# Charger_Relay_Board_rev2.net
KiCad netlist of a schematic drawn in EAGLE
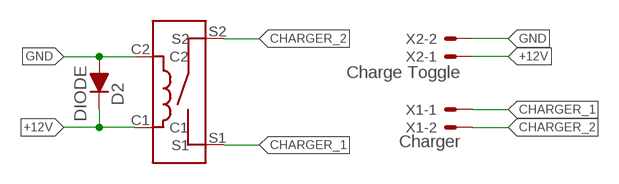
[diagram p0: schematic, sheet 1]

(export (version "E")
  (design (tool "Eeschema 10.0.6"))
  (components
    (comp (ref "D2")
      (value "DIODE")
      (footprint "eagle-import:0805_D")
      (libsource (lib "eagle-import") (part "DIODE0805"))
    )
    (comp (ref "U$1")
      (value "KT12-1A-40L-THT")
      (footprint "eagle-import:KT12-1A-40L-THT")
      (libsource (lib "eagle-import") (part "KT12-1A-40L-THT"))
    )
    (comp (ref "X1")
      (value "Charger")
      (footprint "eagle-import:MINIFIT_5566-2")
      (libsource (lib "eagle-import") (part "CONNECTOR-2"))
    )
    (comp (ref "X2")
      (value "Charge Toggle")
      (footprint "eagle-import:MINIFIT_5566-2")
      (libsource (lib "eagle-import") (part "CONNECTOR-2"))
    )
  )
  (nets
    (net (code "1") (name "+12V") (class "Default")
      (node (ref "D2") (pin "C") (pinfunction "C_C") (pintype "passive"))
      (node (ref "U$1") (pin "C1") (pinfunction "C1_C1") (pintype "bidirectional"))
      (node (ref "X2") (pin "1") (pinfunction "S_1") (pintype "passive"))
    )
    (net (code "2") (name "CHARGER_1") (class "Default")
      (node (ref "U$1") (pin "S1") (pinfunction "S1_S1") (pintype "bidirectional"))
      (node (ref "X1") (pin "1") (pinfunction "S_1") (pintype "passive"))
    )
    (net (code "3") (name "CHARGER_2") (class "Default")
      (node (ref "U$1") (pin "S2") (pinfunction "S2_S2") (pintype "bidirectional"))
      (node (ref "X1") (pin "2") (pinfunction "S_2") (pintype "passive"))
    )
    (net (code "4") (name "GND") (class "Default")
      (node (ref "D2") (pin "A") (pinfunction "A_A") (pintype "passive"))
      (node (ref "U$1") (pin "C2") (pinfunction "C2_C2") (pintype "bidirectional"))
      (node (ref "X2") (pin "2") (pinfunction "S_2") (pintype "passive"))
    )
  )
)
